# MISC.net
KiCad netlist of a schematic drawn in EAGLE
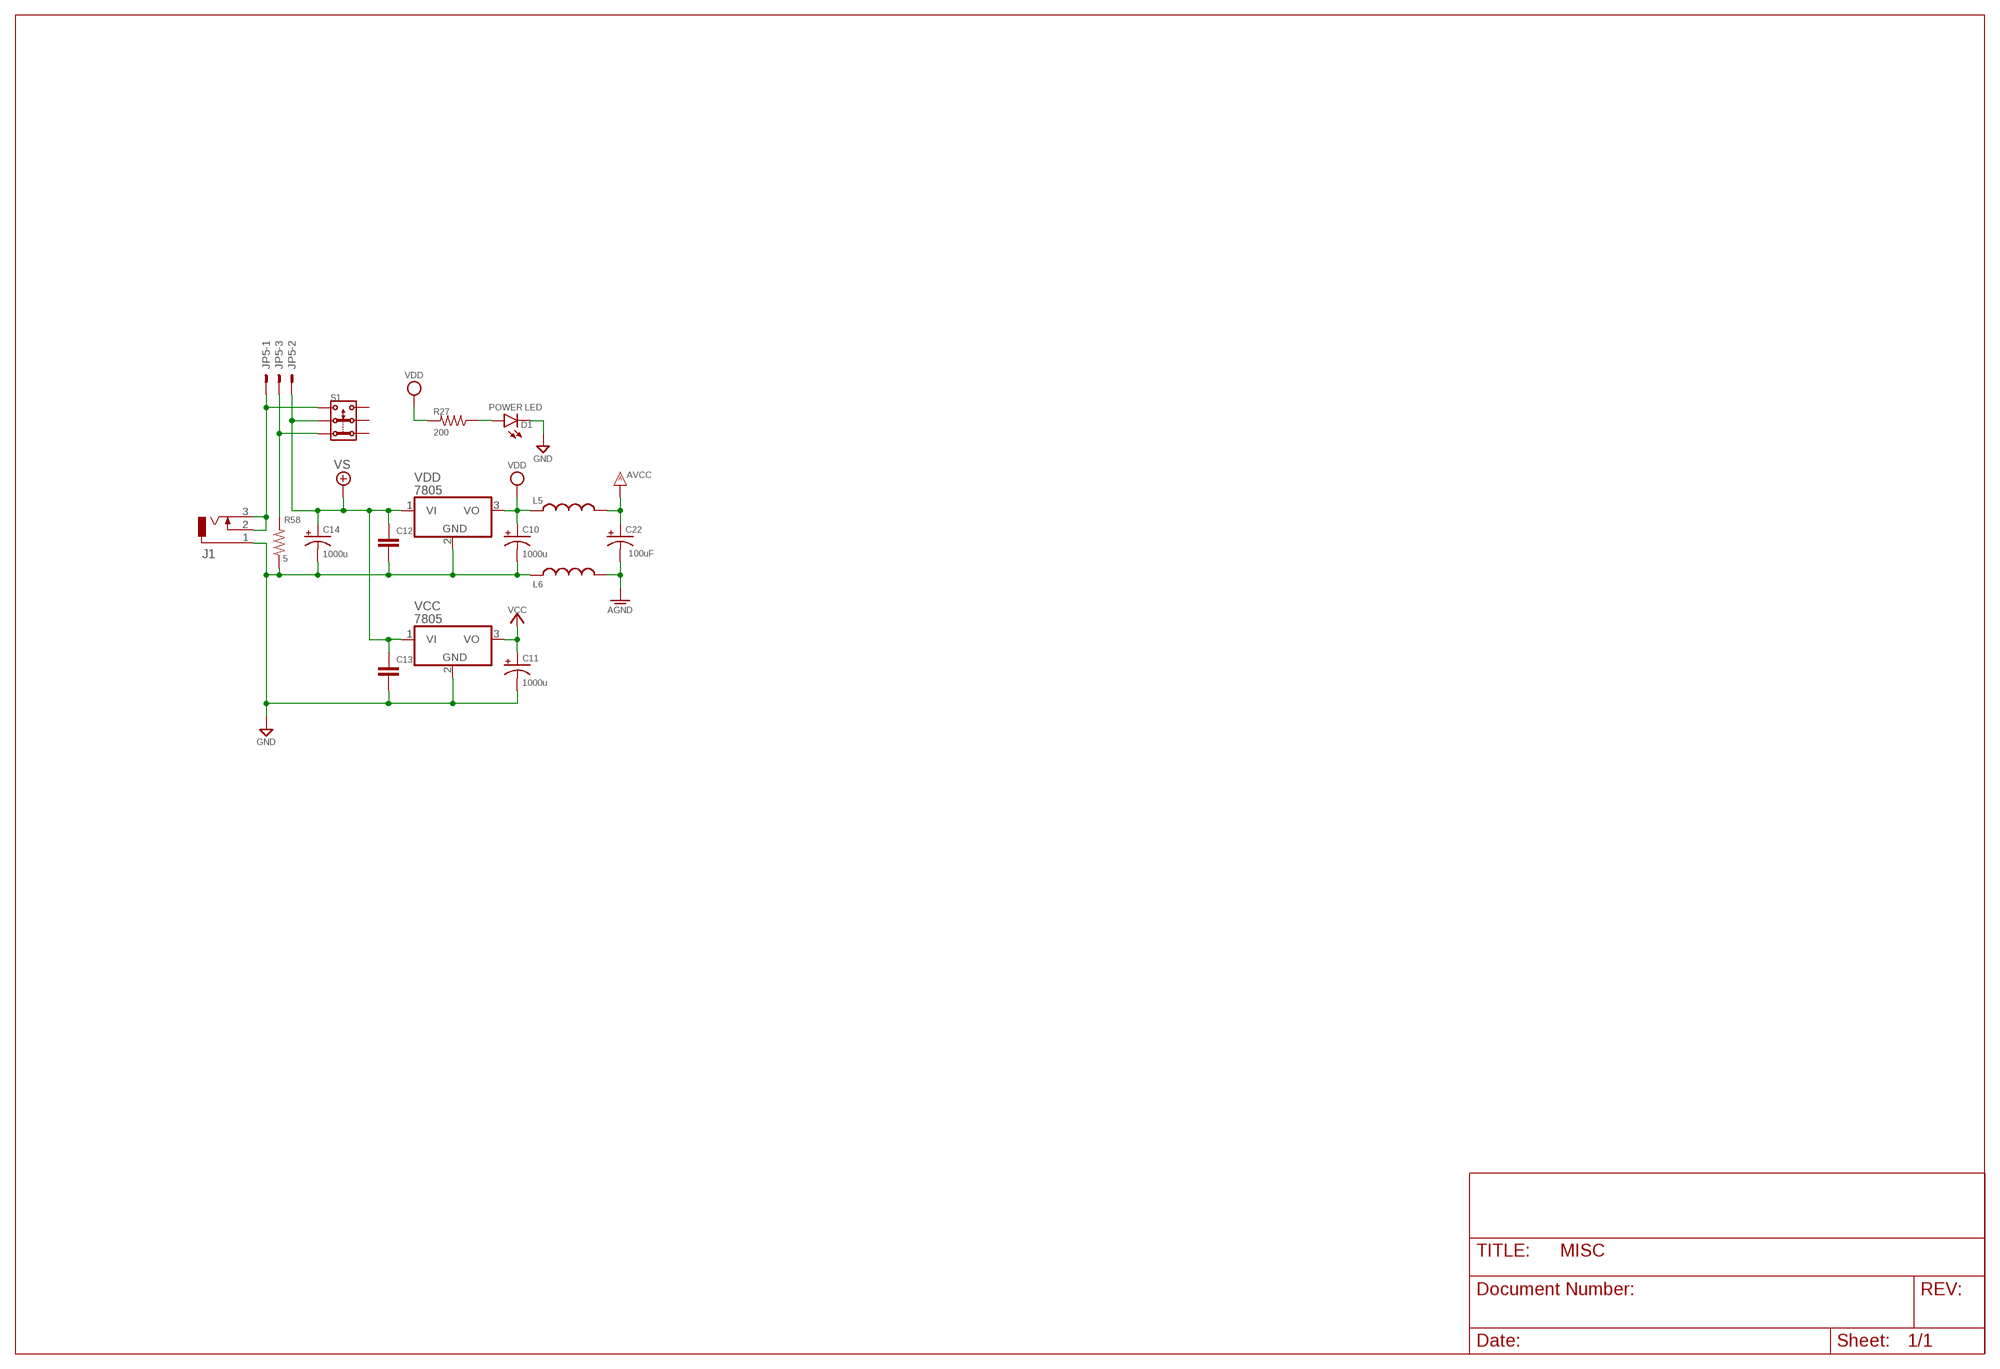
[diagram p0: schematic, sheet 1]

(export (version "E")
  (design (tool "Eeschema 10.0.6"))
  (components
    (comp (ref "C10")
      (value "1000u")
      (footprint "eagle-import:E3,5-10")
      (libsource (lib "eagle-import") (part "CPOL-USE3.5-10"))
    )
    (comp (ref "C11")
      (value "1000u")
      (footprint "eagle-import:E3,5-10")
      (libsource (lib "eagle-import") (part "CPOL-USE3.5-10"))
    )
    (comp (ref "C12")
      (value "C-EUC0805")
      (footprint "eagle-import:C0805")
      (libsource (lib "eagle-import") (part "C-EUC0805"))
    )
    (comp (ref "C13")
      (value "C-EUC0805")
      (footprint "eagle-import:C0805")
      (libsource (lib "eagle-import") (part "C-EUC0805"))
    )
    (comp (ref "C14")
      (value "1000u")
      (footprint "eagle-import:E3,5-10")
      (libsource (lib "eagle-import") (part "CPOL-USE3.5-10"))
    )
    (comp (ref "C22")
      (value "100uF")
      (footprint "eagle-import:TAP5-50")
      (libsource (lib "eagle-import") (part "CPOL-USTAP5-50"))
    )
    (comp (ref "D1")
      (value "POWER LED")
      (footprint "eagle-import:LED3MM")
      (fields (field (name "MF") "VISHAY SEMICONDUCTOR"))
      (libsource (lib "eagle-import") (part "TLLG4400"))
    )
    (comp (ref "J1")
      (value "DCJ0202")
      (footprint "eagle-import:DCJ0202")
      (libsource (lib "eagle-import") (part "DCJ0202"))
    )
    (comp (ref "JP5")
      (value "22-23-2031")
      (footprint "eagle-import:22-23-2031")
      (fields (field (name "MF") "MOLEX"))
      (libsource (lib "eagle-import") (part "22-23-2031"))
    )
    (comp (ref "L5")
      (value "L-US0204/7")
      (footprint "eagle-import:0204_7")
      (libsource (lib "eagle-import") (part "L-US0204/7"))
    )
    (comp (ref "L6")
      (value "L-US0204/7")
      (footprint "eagle-import:0204_7")
      (libsource (lib "eagle-import") (part "L-US0204/7"))
    )
    (comp (ref "R27")
      (value "200")
      (footprint "eagle-import:0204_7")
      (libsource (lib "eagle-import") (part "R-US_0204/7"))
    )
    (comp (ref "R58")
      (value "5")
      (footprint "eagle-import:0204_7")
      (libsource (lib "eagle-import") (part "R-US_0204/7"))
    )
    (comp (ref "S1")
      (value "2P2T")
      (footprint "eagle-import:2P2T")
      (libsource (lib "eagle-import") (part "2P2T"))
    )
    (comp (ref "VCC")
      (value "7805")
      (footprint "eagle-import:TO220V")
      (libsource (lib "eagle-import") (part "78TV05"))
    )
    (comp (ref "VDD")
      (value "7805")
      (footprint "eagle-import:TO220V")
      (libsource (lib "eagle-import") (part "78TV05"))
    )
  )
  (nets
    (net (code "1") (name "AGND") (class "Default")
      (node (ref "C22") (pin "-") (pinfunction "-_-") (pintype "passive"))
      (node (ref "L6") (pin "2") (pinfunction "2_2") (pintype "passive"))
    )
    (net (code "2") (name "AVCC") (class "Default")
      (node (ref "C22") (pin "+") (pinfunction "+_+") (pintype "passive"))
      (node (ref "L5") (pin "2") (pinfunction "2_2") (pintype "passive"))
    )
    (net (code "3") (name "GND") (class "Default")
      (node (ref "C10") (pin "-") (pinfunction "-_-") (pintype "passive"))
      (node (ref "C11") (pin "-") (pinfunction "-_-") (pintype "passive"))
      (node (ref "C12") (pin "2") (pinfunction "2_2") (pintype "passive"))
      (node (ref "C13") (pin "2") (pinfunction "2_2") (pintype "passive"))
      (node (ref "C14") (pin "-") (pinfunction "-_-") (pintype "passive"))
      (node (ref "D1") (pin "K") (pinfunction "C_K") (pintype "passive"))
      (node (ref "J1") (pin "1") (pinfunction "1_1") (pintype "passive"))
      (node (ref "L6") (pin "1") (pinfunction "1_1") (pintype "passive"))
      (node (ref "R58") (pin "1") (pinfunction "1_1") (pintype "passive"))
      (node (ref "VCC") (pin "2") (pinfunction "GND_2") (pintype "passive"))
      (node (ref "VDD") (pin "2") (pinfunction "GND_2") (pintype "passive"))
    )
    (net (code "4") (name "Net-(D1-PadA)") (class "Default")
      (node (ref "D1") (pin "A") (pinfunction "A_A") (pintype "passive"))
      (node (ref "R27") (pin "1") (pinfunction "1_1") (pintype "passive"))
    )
    (net (code "5") (name "Net-(JP5A-S)") (class "Default")
      (node (ref "J1") (pin "2") (pinfunction "2_2") (pintype "passive"))
      (node (ref "J1") (pin "3") (pinfunction "3_3") (pintype "passive"))
      (node (ref "JP5") (pin "1") (pinfunction "S_1") (pintype "passive"))
      (node (ref "S1") (pin "3.1") (pinfunction "3.1_3.1") (pintype "passive"))
    )
    (net (code "6") (name "Net-(JP5C-S)") (class "Default")
      (node (ref "JP5") (pin "3") (pinfunction "S_3") (pintype "passive"))
      (node (ref "R58") (pin "2") (pinfunction "2_2") (pintype "passive"))
      (node (ref "S1") (pin "1.1") (pinfunction "1.1_1.1") (pintype "passive"))
    )
    (net (code "7") (name "VCC") (class "Default")
      (node (ref "C11") (pin "+") (pinfunction "+_+") (pintype "passive"))
      (node (ref "VCC") (pin "3") (pinfunction "VO_3") (pintype "passive"))
    )
    (net (code "8") (name "VDD") (class "Default")
      (node (ref "C10") (pin "+") (pinfunction "+_+") (pintype "passive"))
      (node (ref "L5") (pin "1") (pinfunction "1_1") (pintype "passive"))
      (node (ref "R27") (pin "2") (pinfunction "2_2") (pintype "passive"))
      (node (ref "VDD") (pin "3") (pinfunction "VO_3") (pintype "passive"))
    )
    (net (code "9") (name "VS") (class "Default")
      (node (ref "C12") (pin "1") (pinfunction "1_1") (pintype "passive"))
      (node (ref "C13") (pin "1") (pinfunction "1_1") (pintype "passive"))
      (node (ref "C14") (pin "+") (pinfunction "+_+") (pintype "passive"))
      (node (ref "JP5") (pin "2") (pinfunction "S_2") (pintype "passive"))
      (node (ref "S1") (pin "2.1") (pinfunction "2.1_2.1") (pintype "passive"))
      (node (ref "VCC") (pin "1") (pinfunction "VI_1") (pintype "input"))
      (node (ref "VDD") (pin "1") (pinfunction "VI_1") (pintype "input"))
    )
    (net (code "10") (name "unconnected-(S1-Pad1.2)") (class "Default")
      (node (ref "S1") (pin "1.2") (pinfunction "1.2_1.2") (pintype "passive"))
    )
    (net (code "11") (name "unconnected-(S1-Pad2.2)") (class "Default")
      (node (ref "S1") (pin "2.2") (pinfunction "2.2_2.2") (pintype "passive"))
    )
    (net (code "12") (name "unconnected-(S1-Pad3.2)") (class "Default")
      (node (ref "S1") (pin "3.2") (pinfunction "3.2_3.2") (pintype "passive"))
    )
  )
)
